# nixie-uhr.net
KiCad netlist of a schematic drawn in EAGLE
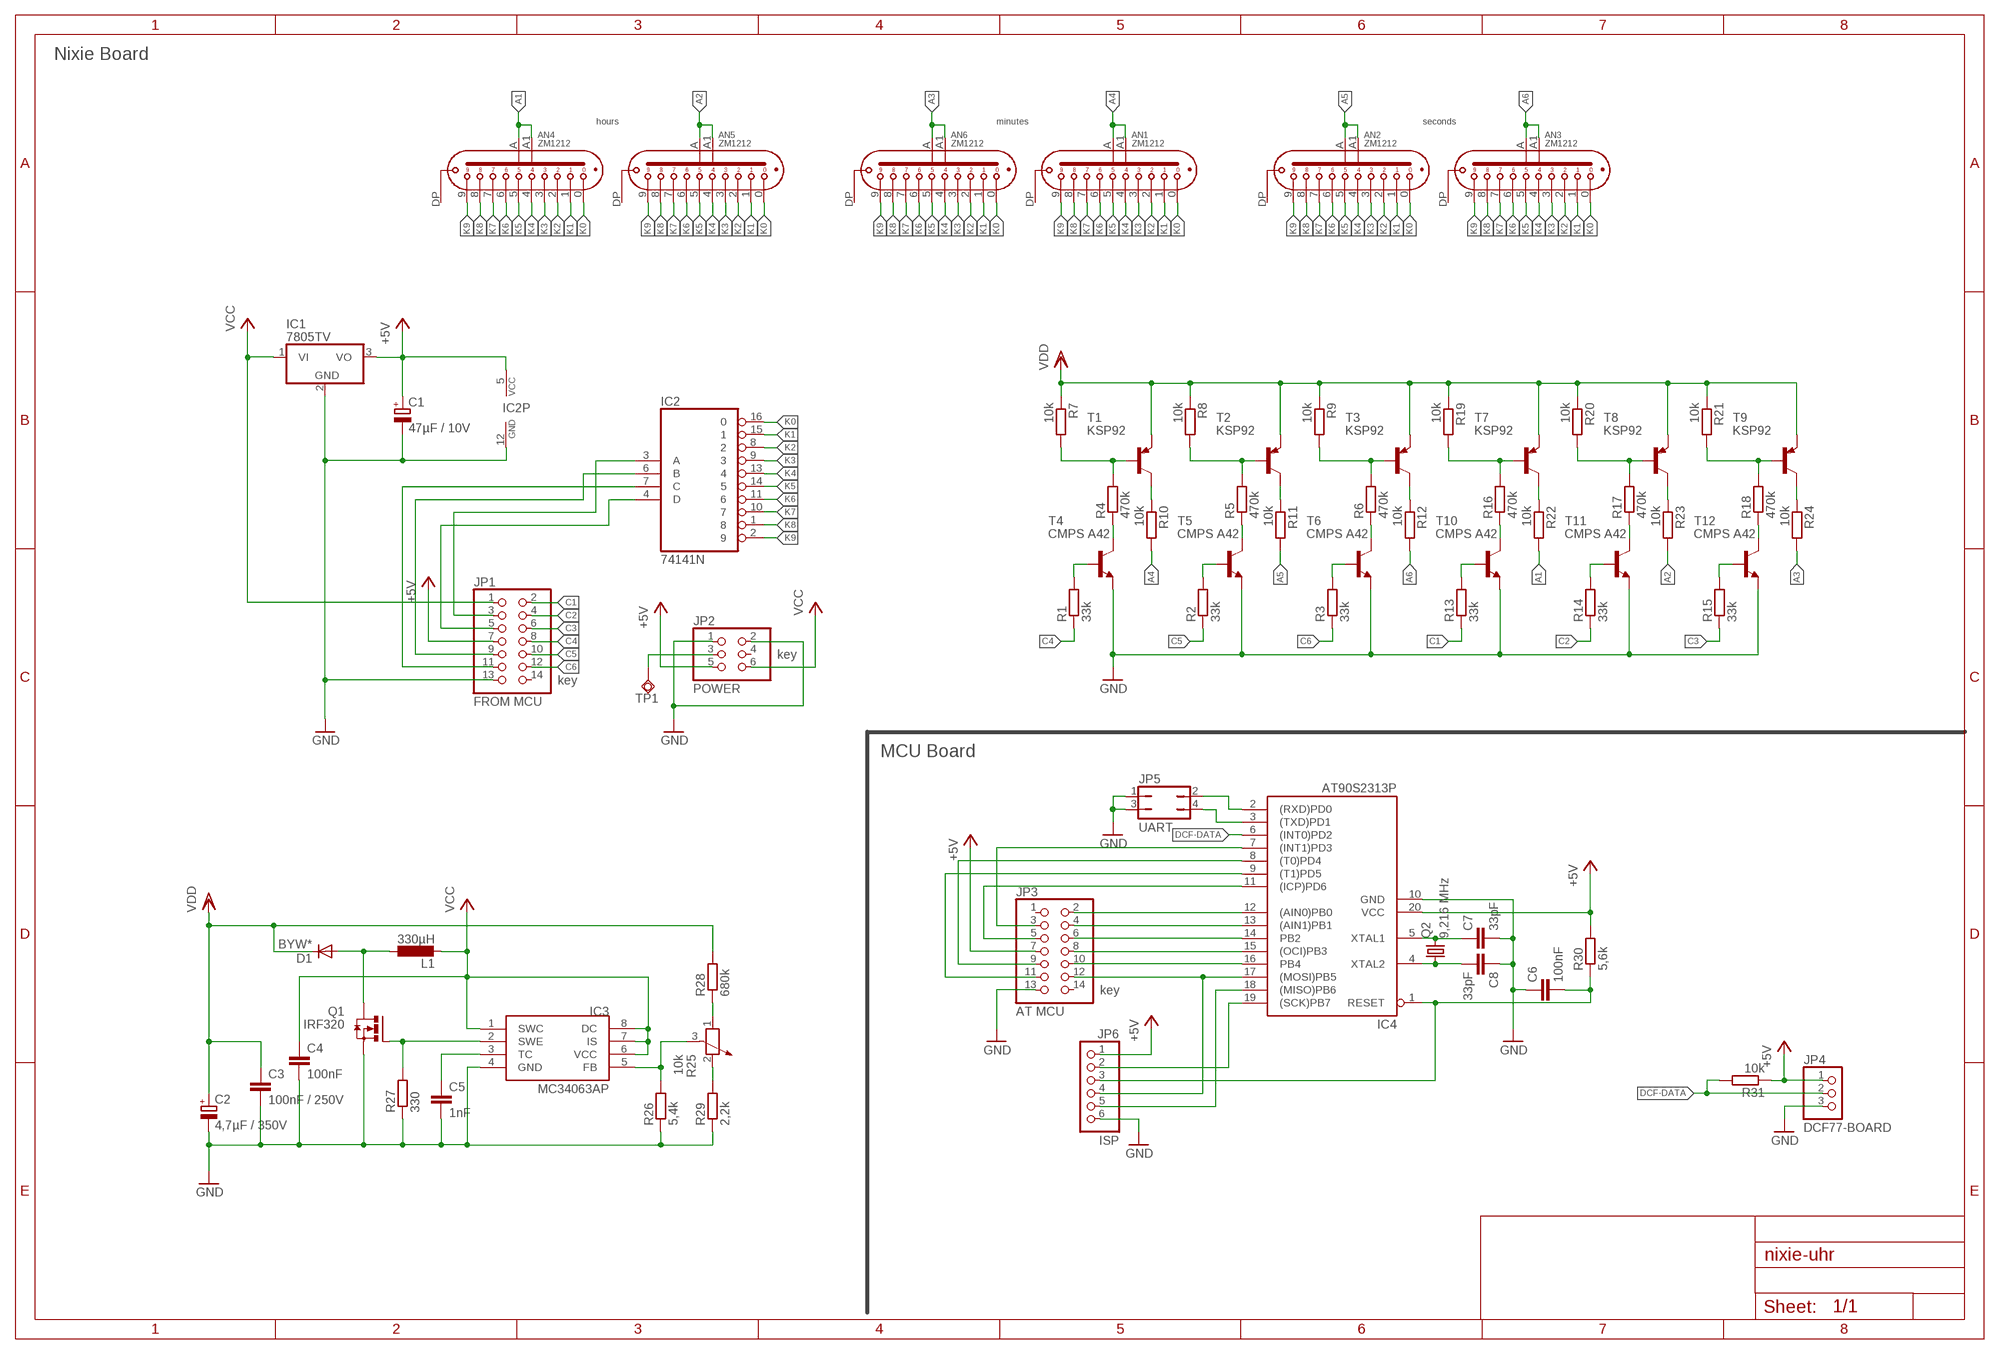
[diagram p0: schematic, sheet 1]

(export (version "E")
  (design (tool "Eeschema 10.0.6"))
  (components
    (comp (ref "AN1")
      (value "ZM1212")
      (footprint "eagle-import:ZM1000")
      (libsource (lib "eagle-import") (part "ZM1000"))
    )
    (comp (ref "AN2")
      (value "ZM1212")
      (footprint "eagle-import:ZM1000")
      (libsource (lib "eagle-import") (part "ZM1000"))
    )
    (comp (ref "AN3")
      (value "ZM1212")
      (footprint "eagle-import:ZM1000")
      (libsource (lib "eagle-import") (part "ZM1000"))
    )
    (comp (ref "AN4")
      (value "ZM1212")
      (footprint "eagle-import:ZM1000")
      (libsource (lib "eagle-import") (part "ZM1000"))
    )
    (comp (ref "AN5")
      (value "ZM1212")
      (footprint "eagle-import:ZM1000")
      (libsource (lib "eagle-import") (part "ZM1000"))
    )
    (comp (ref "AN6")
      (value "ZM1212")
      (footprint "eagle-import:ZM1000")
      (libsource (lib "eagle-import") (part "ZM1000"))
    )
    (comp (ref "C1")
      (value "47µF / 10V")
      (footprint "eagle-import:E2,5-5")
      (libsource (lib "eagle-import") (part "CPOL-EUE2.5-5"))
    )
    (comp (ref "C2")
      (value "4,7µF / 350V")
      (footprint "eagle-import:E30-10")
      (libsource (lib "eagle-import") (part "CPOL-EUE30-10AXIAL"))
    )
    (comp (ref "C3")
      (value "100nF / 250V")
      (footprint "eagle-import:C075-052X106")
      (libsource (lib "eagle-import") (part "C-EU075-052X106"))
    )
    (comp (ref "C4")
      (value "100nF")
      (footprint "eagle-import:C050-024X044")
      (libsource (lib "eagle-import") (part "C-EU050-024X044"))
    )
    (comp (ref "C5")
      (value "1nF")
      (footprint "eagle-import:C050-024X044")
      (libsource (lib "eagle-import") (part "C-EU050-024X044"))
    )
    (comp (ref "C6")
      (value "100nF")
      (footprint "eagle-import:C050-024X044")
      (libsource (lib "eagle-import") (part "C-EU050-024X044"))
    )
    (comp (ref "C7")
      (value "33pF")
      (footprint "eagle-import:C050-024X044")
      (libsource (lib "eagle-import") (part "C-EU050-024X044"))
    )
    (comp (ref "C8")
      (value "33pF")
      (footprint "eagle-import:C050-024X044")
      (libsource (lib "eagle-import") (part "C-EU050-024X044"))
    )
    (comp (ref "D1")
      (value "BYW*")
      (footprint "eagle-import:DO204-10")
      (libsource (lib "eagle-import") (part "BYW32"))
    )
    (comp (ref "IC1")
      (value "7805TV")
      (footprint "eagle-import:TO220V")
      (libsource (lib "eagle-import") (part "78TV05"))
    )
    (comp (ref "IC2")
      (value "74141N")
      (footprint "eagle-import:DIL16")
      (libsource (lib "eagle-import") (part "74141N"))
    )
    (comp (ref "IC3")
      (value "MC34063AP")
      (footprint "eagle-import:DIL08")
      (libsource (lib "eagle-import") (part "MC34063AP"))
    )
    (comp (ref "IC4")
      (value "AT90S2313P")
      (footprint "eagle-import:DIL20")
      (libsource (lib "eagle-import") (part "AT90S2313P"))
    )
    (comp (ref "JP1")
      (value "FROM MCU")
      (footprint "eagle-import:2X07")
      (libsource (lib "eagle-import") (part "PINHD-2X7"))
    )
    (comp (ref "JP2")
      (value "POWER")
      (footprint "eagle-import:2X03")
      (libsource (lib "eagle-import") (part "PINHD-2X3"))
    )
    (comp (ref "JP3")
      (value "AT MCU")
      (footprint "eagle-import:2X07")
      (libsource (lib "eagle-import") (part "PINHD-2X7"))
    )
    (comp (ref "JP4")
      (value "DCF77-BOARD")
      (footprint "eagle-import:1X03")
      (libsource (lib "eagle-import") (part "PINHD-1X3"))
    )
    (comp (ref "JP5")
      (value "UART")
      (footprint "eagle-import:JP2Q")
      (libsource (lib "eagle-import") (part "JP2Q"))
    )
    (comp (ref "JP6")
      (value "ISP")
      (footprint "eagle-import:1X06_90")
      (libsource (lib "eagle-import") (part "PINHD-1X6/90"))
    )
    (comp (ref "L1")
      (value "330µH")
      (footprint "eagle-import:0207_7")
      (libsource (lib "eagle-import") (part "L-EU0207/7"))
    )
    (comp (ref "Q1")
      (value "IRF320")
      (footprint "eagle-import:D2PACK")
      (libsource (lib "eagle-import") (part "IRF3704S"))
    )
    (comp (ref "Q2")
      (value "9,216 MHz")
      (footprint "eagle-import:HC49U-H")
      (libsource (lib "eagle-import") (part "CRYSTALHC49U-H"))
    )
    (comp (ref "R1")
      (value "33k")
      (footprint "eagle-import:0204_5")
      (libsource (lib "eagle-import") (part "R-EU_0204/5"))
    )
    (comp (ref "R2")
      (value "33k")
      (footprint "eagle-import:0204_5")
      (libsource (lib "eagle-import") (part "R-EU_0204/5"))
    )
    (comp (ref "R3")
      (value "33k")
      (footprint "eagle-import:0204_5")
      (libsource (lib "eagle-import") (part "R-EU_0204/5"))
    )
    (comp (ref "R4")
      (value "470k")
      (footprint "eagle-import:0204_5")
      (libsource (lib "eagle-import") (part "R-EU_0204/5"))
    )
    (comp (ref "R5")
      (value "470k")
      (footprint "eagle-import:0204_5")
      (libsource (lib "eagle-import") (part "R-EU_0204/5"))
    )
    (comp (ref "R6")
      (value "470k")
      (footprint "eagle-import:0204_5")
      (libsource (lib "eagle-import") (part "R-EU_0204/5"))
    )
    (comp (ref "R7")
      (value "10k")
      (footprint "eagle-import:0204_5")
      (libsource (lib "eagle-import") (part "R-EU_0204/5"))
    )
    (comp (ref "R8")
      (value "10k")
      (footprint "eagle-import:0204_5")
      (libsource (lib "eagle-import") (part "R-EU_0204/5"))
    )
    (comp (ref "R9")
      (value "10k")
      (footprint "eagle-import:0204_5")
      (libsource (lib "eagle-import") (part "R-EU_0204/5"))
    )
    (comp (ref "R10")
      (value "10k")
      (footprint "eagle-import:0204_5")
      (libsource (lib "eagle-import") (part "R-EU_0204/5"))
    )
    (comp (ref "R11")
      (value "10k")
      (footprint "eagle-import:0204_5")
      (libsource (lib "eagle-import") (part "R-EU_0204/5"))
    )
    (comp (ref "R12")
      (value "10k")
      (footprint "eagle-import:0204_5")
      (libsource (lib "eagle-import") (part "R-EU_0204/5"))
    )
    (comp (ref "R13")
      (value "33k")
      (footprint "eagle-import:0204_5")
      (libsource (lib "eagle-import") (part "R-EU_0204/5"))
    )
    (comp (ref "R14")
      (value "33k")
      (footprint "eagle-import:0204_5")
      (libsource (lib "eagle-import") (part "R-EU_0204/5"))
    )
    (comp (ref "R15")
      (value "33k")
      (footprint "eagle-import:0204_5")
      (libsource (lib "eagle-import") (part "R-EU_0204/5"))
    )
    (comp (ref "R16")
      (value "470k")
      (footprint "eagle-import:0204_5")
      (libsource (lib "eagle-import") (part "R-EU_0204/5"))
    )
    (comp (ref "R17")
      (value "470k")
      (footprint "eagle-import:0204_5")
      (libsource (lib "eagle-import") (part "R-EU_0204/5"))
    )
    (comp (ref "R18")
      (value "470k")
      (footprint "eagle-import:0204_5")
      (libsource (lib "eagle-import") (part "R-EU_0204/5"))
    )
    (comp (ref "R19")
      (value "10k")
      (footprint "eagle-import:0204_5")
      (libsource (lib "eagle-import") (part "R-EU_0204/5"))
    )
    (comp (ref "R20")
      (value "10k")
      (footprint "eagle-import:0204_5")
      (libsource (lib "eagle-import") (part "R-EU_0204/5"))
    )
    (comp (ref "R21")
      (value "10k")
      (footprint "eagle-import:0204_5")
      (libsource (lib "eagle-import") (part "R-EU_0204/5"))
    )
    (comp (ref "R22")
      (value "10k")
      (footprint "eagle-import:0204_5")
      (libsource (lib "eagle-import") (part "R-EU_0204/5"))
    )
    (comp (ref "R23")
      (value "10k")
      (footprint "eagle-import:0204_5")
      (libsource (lib "eagle-import") (part "R-EU_0204/5"))
    )
    (comp (ref "R24")
      (value "10k")
      (footprint "eagle-import:0204_5")
      (libsource (lib "eagle-import") (part "R-EU_0204/5"))
    )
    (comp (ref "R25")
      (value "10k")
      (footprint "eagle-import:PT-SPIN")
      (libsource (lib "eagle-import") (part "POTENTIOMETER_PT_SPIN"))
    )
    (comp (ref "R26")
      (value "5,4k")
      (footprint "eagle-import:0207_7")
      (libsource (lib "eagle-import") (part "R-EU_0207/7"))
    )
    (comp (ref "R27")
      (value "330")
      (footprint "eagle-import:0207_7")
      (libsource (lib "eagle-import") (part "R-EU_0207/7"))
    )
    (comp (ref "R28")
      (value "680k")
      (footprint "eagle-import:0309_12")
      (libsource (lib "eagle-import") (part "R-EU_0309/12"))
    )
    (comp (ref "R29")
      (value "2,2k")
      (footprint "eagle-import:0309_12")
      (libsource (lib "eagle-import") (part "R-EU_0309/12"))
    )
    (comp (ref "R30")
      (value "5,6k")
      (footprint "eagle-import:0204_5")
      (libsource (lib "eagle-import") (part "R-EU_0204/5"))
    )
    (comp (ref "R31")
      (value "10k")
      (footprint "eagle-import:0204_5")
      (libsource (lib "eagle-import") (part "R-EU_0204/5"))
    )
    (comp (ref "T1")
      (value "KSP92")
      (footprint "eagle-import:TO92")
      (libsource (lib "eagle-import") (part "-PNP-TO92"))
    )
    (comp (ref "T2")
      (value "KSP92")
      (footprint "eagle-import:TO92")
      (libsource (lib "eagle-import") (part "-PNP-TO92"))
    )
    (comp (ref "T3")
      (value "KSP92")
      (footprint "eagle-import:TO92")
      (libsource (lib "eagle-import") (part "-PNP-TO92"))
    )
    (comp (ref "T4")
      (value "CMPS A42")
      (footprint "eagle-import:TO92-CBE")
      (libsource (lib "eagle-import") (part "-NPN-TO92-CBEMPSA42"))
    )
    (comp (ref "T5")
      (value "CMPS A42")
      (footprint "eagle-import:TO92-CBE")
      (libsource (lib "eagle-import") (part "-NPN-TO92-CBEMPSA42"))
    )
    (comp (ref "T6")
      (value "CMPS A42")
      (footprint "eagle-import:TO92-CBE")
      (libsource (lib "eagle-import") (part "-NPN-TO92-CBEMPSA42"))
    )
    (comp (ref "T7")
      (value "KSP92")
      (footprint "eagle-import:TO92")
      (libsource (lib "eagle-import") (part "-PNP-TO92"))
    )
    (comp (ref "T8")
      (value "KSP92")
      (footprint "eagle-import:TO92")
      (libsource (lib "eagle-import") (part "-PNP-TO92"))
    )
    (comp (ref "T9")
      (value "KSP92")
      (footprint "eagle-import:TO92")
      (libsource (lib "eagle-import") (part "-PNP-TO92"))
    )
    (comp (ref "T10")
      (value "CMPS A42")
      (footprint "eagle-import:TO92-CBE")
      (libsource (lib "eagle-import") (part "-NPN-TO92-CBEMPSA42"))
    )
    (comp (ref "T11")
      (value "CMPS A42")
      (footprint "eagle-import:TO92-CBE")
      (libsource (lib "eagle-import") (part "-NPN-TO92-CBEMPSA42"))
    )
    (comp (ref "T12")
      (value "CMPS A42")
      (footprint "eagle-import:TO92-CBE")
      (libsource (lib "eagle-import") (part "-NPN-TO92-CBEMPSA42"))
    )
    (comp (ref "TP1")
      (value "TPSQPAD1-17")
      (footprint "eagle-import:P1-17")
      (libsource (lib "eagle-import") (part "TPSQPAD1-17"))
    )
  )
  (nets
    (net (code "1") (name "+5V") (class "Default")
      (node (ref "C1") (pin "+") (pinfunction "+_+") (pintype "passive"))
      (node (ref "IC1") (pin "3") (pinfunction "VO_3") (pintype "passive"))
      (node (ref "IC2") (pin "5") (pinfunction "VCC_5") (pintype "power_in"))
      (node (ref "IC4") (pin "20") (pinfunction "VCC_20") (pintype "power_in"))
      (node (ref "JP1") (pin "7") (pinfunction "7_7") (pintype "passive"))
      (node (ref "JP2") (pin "5") (pinfunction "5_5") (pintype "passive"))
      (node (ref "JP3") (pin "7") (pinfunction "7_7") (pintype "passive"))
      (node (ref "JP4") (pin "1") (pinfunction "1_1") (pintype "passive"))
      (node (ref "JP6") (pin "1") (pinfunction "1_1") (pintype "passive"))
      (node (ref "R30") (pin "2") (pinfunction "2_2") (pintype "passive"))
      (node (ref "R31") (pin "1") (pinfunction "1_1") (pintype "passive"))
    )
    (net (code "2") (name "A1") (class "Default")
      (node (ref "AN4") (pin "A") (pinfunction "A1_A") (pintype "passive"))
      (node (ref "AN4") (pin "A1") (pinfunction "A2_A1") (pintype "passive"))
      (node (ref "R22") (pin "2") (pinfunction "2_2") (pintype "passive"))
    )
    (net (code "3") (name "A2") (class "Default")
      (node (ref "AN5") (pin "A") (pinfunction "A1_A") (pintype "passive"))
      (node (ref "AN5") (pin "A1") (pinfunction "A2_A1") (pintype "passive"))
      (node (ref "R23") (pin "2") (pinfunction "2_2") (pintype "passive"))
    )
    (net (code "4") (name "A3") (class "Default")
      (node (ref "AN6") (pin "A") (pinfunction "A1_A") (pintype "passive"))
      (node (ref "AN6") (pin "A1") (pinfunction "A2_A1") (pintype "passive"))
      (node (ref "R24") (pin "2") (pinfunction "2_2") (pintype "passive"))
    )
    (net (code "5") (name "A4") (class "Default")
      (node (ref "AN1") (pin "A") (pinfunction "A1_A") (pintype "passive"))
      (node (ref "AN1") (pin "A1") (pinfunction "A2_A1") (pintype "passive"))
      (node (ref "R10") (pin "2") (pinfunction "2_2") (pintype "passive"))
    )
    (net (code "6") (name "A5") (class "Default")
      (node (ref "AN2") (pin "A") (pinfunction "A1_A") (pintype "passive"))
      (node (ref "AN2") (pin "A1") (pinfunction "A2_A1") (pintype "passive"))
      (node (ref "R11") (pin "2") (pinfunction "2_2") (pintype "passive"))
    )
    (net (code "7") (name "A6") (class "Default")
      (node (ref "AN3") (pin "A") (pinfunction "A1_A") (pintype "passive"))
      (node (ref "AN3") (pin "A1") (pinfunction "A2_A1") (pintype "passive"))
      (node (ref "R12") (pin "2") (pinfunction "2_2") (pintype "passive"))
    )
    (net (code "8") (name "C1") (class "Default")
      (node (ref "JP1") (pin "2") (pinfunction "2_2") (pintype "passive"))
      (node (ref "R13") (pin "1") (pinfunction "1_1") (pintype "passive"))
    )
    (net (code "9") (name "C2") (class "Default")
      (node (ref "JP1") (pin "4") (pinfunction "4_4") (pintype "passive"))
      (node (ref "R14") (pin "1") (pinfunction "1_1") (pintype "passive"))
    )
    (net (code "10") (name "C3") (class "Default")
      (node (ref "JP1") (pin "6") (pinfunction "6_6") (pintype "passive"))
      (node (ref "R15") (pin "1") (pinfunction "1_1") (pintype "passive"))
    )
    (net (code "11") (name "C4") (class "Default")
      (node (ref "JP1") (pin "8") (pinfunction "8_8") (pintype "passive"))
      (node (ref "R1") (pin "1") (pinfunction "1_1") (pintype "passive"))
    )
    (net (code "12") (name "C5") (class "Default")
      (node (ref "JP1") (pin "10") (pinfunction "10_10") (pintype "passive"))
      (node (ref "R2") (pin "1") (pinfunction "1_1") (pintype "passive"))
    )
    (net (code "13") (name "C6") (class "Default")
      (node (ref "JP1") (pin "12") (pinfunction "12_12") (pintype "passive"))
      (node (ref "R3") (pin "1") (pinfunction "1_1") (pintype "passive"))
    )
    (net (code "14") (name "DCF-DATA") (class "Default")
      (node (ref "IC4") (pin "6") (pinfunction "(INT0)PD2_6") (pintype "bidirectional"))
      (node (ref "JP4") (pin "2") (pinfunction "2_2") (pintype "passive"))
      (node (ref "R31") (pin "2") (pinfunction "2_2") (pintype "passive"))
    )
    (net (code "15") (name "GND") (class "Default")
      (node (ref "C1") (pin "-") (pinfunction "-_-") (pintype "passive"))
      (node (ref "C2") (pin "-") (pinfunction "-_-") (pintype "passive"))
      (node (ref "C3") (pin "2") (pinfunction "2_2") (pintype "passive"))
      (node (ref "C4") (pin "2") (pinfunction "2_2") (pintype "passive"))
      (node (ref "C5") (pin "2") (pinfunction "2_2") (pintype "passive"))
      (node (ref "C6") (pin "1") (pinfunction "1_1") (pintype "passive"))
      (node (ref "C7") (pin "2") (pinfunction "2_2") (pintype "passive"))
      (node (ref "C8") (pin "1") (pinfunction "1_1") (pintype "passive"))
      (node (ref "IC1") (pin "2") (pinfunction "GND_2") (pintype "passive"))
      (node (ref "IC2") (pin "12") (pinfunction "GND_12") (pintype "power_in"))
      (node (ref "IC3") (pin "4") (pinfunction "GND_4") (pintype "passive"))
      (node (ref "IC4") (pin "10") (pinfunction "GND_10") (pintype "power_in"))
      (node (ref "JP1") (pin "13") (pinfunction "13_13") (pintype "passive"))
      (node (ref "JP2") (pin "1") (pinfunction "1_1") (pintype "passive"))
      (node (ref "JP2") (pin "2") (pinfunction "2_2") (pintype "passive"))
      (node (ref "JP3") (pin "13") (pinfunction "13_13") (pintype "passive"))
      (node (ref "JP4") (pin "3") (pinfunction "3_3") (pintype "passive"))
      (node (ref "JP5") (pin "1") (pinfunction "1_1") (pintype "passive"))
      (node (ref "JP5") (pin "3") (pinfunction "3_3") (pintype "passive"))
      (node (ref "JP6") (pin "6") (pinfunction "6_6") (pintype "passive"))
      (node (ref "Q1") (pin "3") (pinfunction "S_3") (pintype "passive"))
      (node (ref "R26") (pin "1") (pinfunction "1_1") (pintype "passive"))
      (node (ref "R27") (pin "1") (pinfunction "1_1") (pintype "passive"))
      (node (ref "R29") (pin "1") (pinfunction "1_1") (pintype "passive"))
      (node (ref "T10") (pin "E") (pinfunction "E_E") (pintype "passive"))
      (node (ref "T11") (pin "E") (pinfunction "E_E") (pintype "passive"))
      (node (ref "T12") (pin "E") (pinfunction "E_E") (pintype "passive"))
      (node (ref "T4") (pin "E") (pinfunction "E_E") (pintype "passive"))
      (node (ref "T5") (pin "E") (pinfunction "E_E") (pintype "passive"))
      (node (ref "T6") (pin "E") (pinfunction "E_E") (pintype "passive"))
    )
    (net (code "16") (name "K0") (class "Default")
      (node (ref "AN1") (pin "0") (pinfunction "0_0") (pintype "passive"))
      (node (ref "AN2") (pin "0") (pinfunction "0_0") (pintype "passive"))
      (node (ref "AN3") (pin "0") (pinfunction "0_0") (pintype "passive"))
      (node (ref "AN4") (pin "0") (pinfunction "0_0") (pintype "passive"))
      (node (ref "AN5") (pin "0") (pinfunction "0_0") (pintype "passive"))
      (node (ref "AN6") (pin "0") (pinfunction "0_0") (pintype "passive"))
      (node (ref "IC2") (pin "16") (pinfunction "0_16") (pintype "open_collector"))
    )
    (net (code "17") (name "K1") (class "Default")
      (node (ref "AN1") (pin "1") (pinfunction "1_1") (pintype "passive"))
      (node (ref "AN2") (pin "1") (pinfunction "1_1") (pintype "passive"))
      (node (ref "AN3") (pin "1") (pinfunction "1_1") (pintype "passive"))
      (node (ref "AN4") (pin "1") (pinfunction "1_1") (pintype "passive"))
      (node (ref "AN5") (pin "1") (pinfunction "1_1") (pintype "passive"))
      (node (ref "AN6") (pin "1") (pinfunction "1_1") (pintype "passive"))
      (node (ref "IC2") (pin "15") (pinfunction "1_15") (pintype "open_collector"))
    )
    (net (code "18") (name "K2") (class "Default")
      (node (ref "AN1") (pin "2") (pinfunction "2_2") (pintype "passive"))
      (node (ref "AN2") (pin "2") (pinfunction "2_2") (pintype "passive"))
      (node (ref "AN3") (pin "2") (pinfunction "2_2") (pintype "passive"))
      (node (ref "AN4") (pin "2") (pinfunction "2_2") (pintype "passive"))
      (node (ref "AN5") (pin "2") (pinfunction "2_2") (pintype "passive"))
      (node (ref "AN6") (pin "2") (pinfunction "2_2") (pintype "passive"))
      (node (ref "IC2") (pin "8") (pinfunction "2_8") (pintype "open_collector"))
    )
    (net (code "19") (name "K3") (class "Default")
      (node (ref "AN1") (pin "3") (pinfunction "3_3") (pintype "passive"))
      (node (ref "AN2") (pin "3") (pinfunction "3_3") (pintype "passive"))
      (node (ref "AN3") (pin "3") (pinfunction "3_3") (pintype "passive"))
      (node (ref "AN4") (pin "3") (pinfunction "3_3") (pintype "passive"))
      (node (ref "AN5") (pin "3") (pinfunction "3_3") (pintype "passive"))
      (node (ref "AN6") (pin "3") (pinfunction "3_3") (pintype "passive"))
      (node (ref "IC2") (pin "9") (pinfunction "3_9") (pintype "open_collector"))
    )
    (net (code "20") (name "K4") (class "Default")
      (node (ref "AN1") (pin "4") (pinfunction "4_4") (pintype "passive"))
      (node (ref "AN2") (pin "4") (pinfunction "4_4") (pintype "passive"))
      (node (ref "AN3") (pin "4") (pinfunction "4_4") (pintype "passive"))
      (node (ref "AN4") (pin "4") (pinfunction "4_4") (pintype "passive"))
      (node (ref "AN5") (pin "4") (pinfunction "4_4") (pintype "passive"))
      (node (ref "AN6") (pin "4") (pinfunction "4_4") (pintype "passive"))
      (node (ref "IC2") (pin "13") (pinfunction "4_13") (pintype "open_collector"))
    )
    (net (code "21") (name "K5") (class "Default")
      (node (ref "AN1") (pin "5") (pinfunction "5_5") (pintype "passive"))
      (node (ref "AN2") (pin "5") (pinfunction "5_5") (pintype "passive"))
      (node (ref "AN3") (pin "5") (pinfunction "5_5") (pintype "passive"))
      (node (ref "AN4") (pin "5") (pinfunction "5_5") (pintype "passive"))
      (node (ref "AN5") (pin "5") (pinfunction "5_5") (pintype "passive"))
      (node (ref "AN6") (pin "5") (pinfunction "5_5") (pintype "passive"))
      (node (ref "IC2") (pin "14") (pinfunction "5_14") (pintype "open_collector"))
    )
    (net (code "22") (name "K6") (class "Default")
      (node (ref "AN1") (pin "6") (pinfunction "6_6") (pintype "passive"))
      (node (ref "AN2") (pin "6") (pinfunction "6_6") (pintype "passive"))
      (node (ref "AN3") (pin "6") (pinfunction "6_6") (pintype "passive"))
      (node (ref "AN4") (pin "6") (pinfunction "6_6") (pintype "passive"))
      (node (ref "AN5") (pin "6") (pinfunction "6_6") (pintype "passive"))
      (node (ref "AN6") (pin "6") (pinfunction "6_6") (pintype "passive"))
      (node (ref "IC2") (pin "11") (pinfunction "6_11") (pintype "open_collector"))
    )
    (net (code "23") (name "K7") (class "Default")
      (node (ref "AN1") (pin "7") (pinfunction "7_7") (pintype "passive"))
      (node (ref "AN2") (pin "7") (pinfunction "7_7") (pintype "passive"))
      (node (ref "AN3") (pin "7") (pinfunction "7_7") (pintype "passive"))
      (node (ref "AN4") (pin "7") (pinfunction "7_7") (pintype "passive"))
      (node (ref "AN5") (pin "7") (pinfunction "7_7") (pintype "passive"))
      (node (ref "AN6") (pin "7") (pinfunction "7_7") (pintype "passive"))
      (node (ref "IC2") (pin "10") (pinfunction "7_10") (pintype "open_collector"))
    )
    (net (code "24") (name "K8") (class "Default")
      (node (ref "AN1") (pin "8") (pinfunction "8_8") (pintype "passive"))
      (node (ref "AN2") (pin "8") (pinfunction "8_8") (pintype "passive"))
      (node (ref "AN3") (pin "8") (pinfunction "8_8") (pintype "passive"))
      (node (ref "AN4") (pin "8") (pinfunction "8_8") (pintype "passive"))
      (node (ref "AN5") (pin "8") (pinfunction "8_8") (pintype "passive"))
      (node (ref "AN6") (pin "8") (pinfunction "8_8") (pintype "passive"))
      (node (ref "IC2") (pin "1") (pinfunction "8_1") (pintype "open_collector"))
    )
    (net (code "25") (name "K9") (class "Default")
      (node (ref "AN1") (pin "9") (pinfunction "9_9") (pintype "passive"))
      (node (ref "AN2") (pin "9") (pinfunction "9_9") (pintype "passive"))
      (node (ref "AN3") (pin "9") (pinfunction "9_9") (pintype "passive"))
      (node (ref "AN4") (pin "9") (pinfunction "9_9") (pintype "passive"))
      (node (ref "AN5") (pin "9") (pinfunction "9_9") (pintype "passive"))
      (node (ref "AN6") (pin "9") (pinfunction "9_9") (pintype "passive"))
      (node (ref "IC2") (pin "2") (pinfunction "9_2") (pintype "open_collector"))
    )
    (net (code "26") (name "Net-(IC2A-A)") (class "Default")
      (node (ref "IC2") (pin "3") (pinfunction "A_3") (pintype "input"))
      (node (ref "JP1") (pin "3") (pinfunction "3_3") (pintype "passive"))
    )
    (net (code "27") (name "Net-(IC2A-B)") (class "Default")
      (node (ref "IC2") (pin "6") (pinfunction "B_6") (pintype "input"))
      (node (ref "JP1") (pin "9") (pinfunction "9_9") (pintype "passive"))
    )
    (net (code "28") (name "Net-(IC2A-C)") (class "Default")
      (node (ref "IC2") (pin "7") (pinfunction "C_7") (pintype "input"))
      (node (ref "JP1") (pin "11") (pinfunction "11_11") (pintype "passive"))
    )
    (net (code "29") (name "Net-(IC2A-D)") (class "Default")
      (node (ref "IC2") (pin "4") (pinfunction "D_4") (pintype "input"))
      (node (ref "JP1") (pin "5") (pinfunction "5_5") (pintype "passive"))
    )
    (net (code "30") (name "Net-(IC3-FB)") (class "Default")
      (node (ref "IC3") (pin "5") (pinfunction "FB_5") (pintype "passive"))
      (node (ref "R25") (pin "3") (pinfunction "3_3") (pintype "passive"))
      (node (ref "R26") (pin "2") (pinfunction "2_2") (pintype "passive"))
    )
    (net (code "31") (name "Net-(IC3-SWE)") (class "Default")
      (node (ref "IC3") (pin "2") (pinfunction "SWE_2") (pintype "passive"))
      (node (ref "Q1") (pin "1") (pinfunction "G_1") (pintype "passive"))
      (node (ref "R27") (pin "2") (pinfunction "2_2") (pintype "passive"))
    )
    (net (code "32") (name "Net-(IC3-TC)") (class "Default")
      (node (ref "C5") (pin "1") (pinfunction "1_1") (pintype "passive"))
      (node (ref "IC3") (pin "3") (pinfunction "TC_3") (pintype "passive"))
    )
    (net (code "33") (name "Net-(IC4-(AIN0)PB0)") (class "Default")
      (node (ref "IC4") (pin "12") (pinfunction "(AIN0)PB0_12") (pintype "bidirectional"))
      (node (ref "JP3") (pin "2") (pinfunction "2_2") (pintype "passive"))
    )
    (net (code "34") (name "Net-(IC4-(AIN1)PB1)") (class "Default")
      (node (ref "IC4") (pin "13") (pinfunction "(AIN1)PB1_13") (pintype "bidirectional"))
      (node (ref "JP3") (pin "4") (pinfunction "4_4") (pintype "passive"))
    )
    (net (code "35") (name "Net-(IC4-(ICP)PD6)") (class "Default")
      (node (ref "IC4") (pin "11") (pinfunction "(ICP)PD6_11") (pintype "bidirectional"))
      (node (ref "JP3") (pin "5") (pinfunction "5_5") (pintype "passive"))
    )
    (net (code "36") (name "Net-(IC4-(INT1)PD3)") (class "Default")
      (node (ref "IC4") (pin "7") (pinfunction "(INT1)PD3_7") (pintype "bidirectional"))
      (node (ref "JP3") (pin "3") (pinfunction "3_3") (pintype "passive"))
    )
    (net (code "37") (name "Net-(IC4-(MISO)PB6)") (class "Default")
      (node (ref "IC4") (pin "18") (pinfunction "(MISO)PB6_18") (pintype "bidirectional"))
      (node (ref "JP6") (pin "5") (pinfunction "5_5") (pintype "passive"))
    )
    (net (code "38") (name "Net-(IC4-(MOSI)PB5)") (class "Default")
      (node (ref "IC4") (pin "17") (pinfunction "(MOSI)PB5_17") (pintype "bidirectional"))
      (node (ref "JP3") (pin "12") (pinfunction "12_12") (pintype "passive"))
      (node (ref "JP6") (pin "4") (pinfunction "4_4") (pintype "passive"))
    )
    (net (code "39") (name "Net-(IC4-(OCI)PB3)") (class "Default")
      (node (ref "IC4") (pin "15") (pinfunction "(OCI)PB3_15") (pintype "bidirectional"))
      (node (ref "JP3") (pin "8") (pinfunction "8_8") (pintype "passive"))
    )
    (net (code "40") (name "Net-(IC4-(RXD)PD0)") (class "Default")
      (node (ref "IC4") (pin "2") (pinfunction "(RXD)PD0_2") (pintype "bidirectional"))
      (node (ref "JP5") (pin "2") (pinfunction "2_2") (pintype "passive"))
    )
    (net (code "41") (name "Net-(IC4-(SCK)PB7)") (class "Default")
      (node (ref "IC4") (pin "19") (pinfunction "(SCK)PB7_19") (pintype "bidirectional"))
      (node (ref "JP6") (pin "2") (pinfunction "2_2") (pintype "passive"))
    )
    (net (code "42") (name "Net-(IC4-(T0)PD4)") (class "Default")
      (node (ref "IC4") (pin "8") (pinfunction "(T0)PD4_8") (pintype "bidirectional"))
      (node (ref "JP3") (pin "9") (pinfunction "9_9") (pintype "passive"))
    )
    (net (code "43") (name "Net-(IC4-(T1)PD5)") (class "Default")
      (node (ref "IC4") (pin "9") (pinfunction "(T1)PD5_9") (pintype "bidirectional"))
      (node (ref "JP3") (pin "11") (pinfunction "11_11") (pintype "passive"))
    )
    (net (code "44") (name "Net-(IC4-(TXD)PD1)") (class "Default")
      (node (ref "IC4") (pin "3") (pinfunction "(TXD)PD1_3") (pintype "bidirectional"))
      (node (ref "JP5") (pin "4") (pinfunction "4_4") (pintype "passive"))
    )
    (net (code "45") (name "Net-(IC4-PB2)") (class "Default")
      (node (ref "IC4") (pin "14") (pinfunction "PB2_14") (pintype "bidirectional"))
      (node (ref "JP3") (pin "6") (pinfunction "6_6") (pintype "passive"))
    )
    (net (code "46") (name "Net-(IC4-PB4)") (class "Default")
      (node (ref "IC4") (pin "16") (pinfunction "PB4_16") (pintype "bidirectional"))
      (node (ref "JP3") (pin "10") (pinfunction "10_10") (pintype "passive"))
    )
    (net (code "47") (name "Net-(IC4-RESET)") (class "Default")
      (node (ref "C6") (pin "2") (pinfunction "2_2") (pintype "passive"))
      (node (ref "IC4") (pin "1") (pinfunction "RESET_1") (pintype "bidirectional"))
      (node (ref "JP6") (pin "3") (pinfunction "3_3") (pintype "passive"))
      (node (ref "R30") (pin "1") (pinfunction "1_1") (pintype "passive"))
    )
    (net (code "48") (name "Net-(IC4-XTAL1)") (class "Default")
      (node (ref "C7") (pin "1") (pinfunction "1_1") (pintype "passive"))
      (node (ref "IC4") (pin "5") (pinfunction "XTAL1_5") (pintype "bidirectional"))
      (node (ref "Q2") (pin "2") (pinfunction "2_2") (pintype "passive"))
    )
    (net (code "49") (name "Net-(IC4-XTAL2)") (class "Default")
      (node (ref "C8") (pin "2") (pinfunction "2_2") (pintype "passive"))
      (node (ref "IC4") (pin "4") (pinfunction "XTAL2_4") (pintype "bidirectional"))
      (node (ref "Q2") (pin "1") (pinfunction "1_1") (pintype "passive"))
    )
    (net (code "50") (name "Net-(JP2-Pad3)") (class "Default")
      (node (ref "JP2") (pin "3") (pinfunction "3_3") (pintype "passive"))
      (node (ref "TP1") (pin "TP") (pinfunction "TP_TP") (pintype "input"))
    )
    (net (code "51") (name "Net-(Q1-D)") (class "Default")
      (node (ref "D1") (pin "A") (pinfunction "A_A") (pintype "passive"))
      (node (ref "L1") (pin "1") (pinfunction "1_1") (pintype "passive"))
      (node (ref "Q1") (pin "2") (pinfunction "D_2") (pintype "passive"))
    )
    (net (code "52") (name "Net-(R1-Pad2)") (class "Default")
      (node (ref "R1") (pin "2") (pinfunction "2_2") (pintype "passive"))
      (node (ref "T4") (pin "B") (pinfunction "B_B") (pintype "passive"))
    )
    (net (code "53") (name "Net-(R2-Pad2)") (class "Default")
      (node (ref "R2") (pin "2") (pinfunction "2_2") (pintype "passive"))
      (node (ref "T5") (pin "B") (pinfunction "B_B") (pintype "passive"))
    )
    (net (code "54") (name "Net-(R3-Pad2)") (class "Default")
      (node (ref "R3") (pin "2") (pinfunction "2_2") (pintype "passive"))
      (node (ref "T6") (pin "B") (pinfunction "B_B") (pintype "passive"))
    )
    (net (code "55") (name "Net-(R4-Pad1)") (class "Default")
      (node (ref "R4") (pin "1") (pinfunction "1_1") (pintype "passive"))
      (node (ref "T4") (pin "C") (pinfunction "C_C") (pintype "passive"))
    )
    (net (code "56") (name "Net-(R5-Pad1)") (class "Default")
      (node (ref "R5") (pin "1") (pinfunction "1_1") (pintype "passive"))
      (node (ref "T5") (pin "C") (pinfunction "C_C") (pintype "passive"))
    )
    (net (code "57") (name "Net-(R6-Pad1)") (class "Default")
      (node (ref "R6") (pin "1") (pinfunction "1_1") (pintype "passive"))
      (node (ref "T6") (pin "C") (pinfunction "C_C") (pintype "passive"))
    )
    (net (code "58") (name "Net-(R13-Pad2)") (class "Default")
      (node (ref "R13") (pin "2") (pinfunction "2_2") (pintype "passive"))
      (node (ref "T10") (pin "B") (pinfunction "B_B") (pintype "passive"))
    )
    (net (code "59") (name "Net-(R14-Pad2)") (class "Default")
      (node (ref "R14") (pin "2") (pinfunction "2_2") (pintype "passive"))
      (node (ref "T11") (pin "B") (pinfunction "B_B") (pintype "passive"))
    )
    (net (code "60") (name "Net-(R15-Pad2)") (class "Default")
      (node (ref "R15") (pin "2") (pinfunction "2_2") (pintype "passive"))
      (node (ref "T12") (pin "B") (pinfunction "B_B") (pintype "passive"))
    )
    (net (code "61") (name "Net-(R16-Pad1)") (class "Default")
      (node (ref "R16") (pin "1") (pinfunction "1_1") (pintype "passive"))
      (node (ref "T10") (pin "C") (pinfunction "C_C") (pintype "passive"))
    )
    (net (code "62") (name "Net-(R17-Pad1)") (class "Default")
      (node (ref "R17") (pin "1") (pinfunction "1_1") (pintype "passive"))
      (node (ref "T11") (pin "C") (pinfunction "C_C") (pintype "passive"))
    )
    (net (code "63") (name "Net-(R18-Pad1)") (class "Default")
      (node (ref "R18") (pin "1") (pinfunction "1_1") (pintype "passive"))
      (node (ref "T12") (pin "C") (pinfunction "C_C") (pintype "passive"))
    )
    (net (code "64") (name "Net-(R25-Pad1)") (class "Default")
      (node (ref "R25") (pin "1") (pinfunction "1_1") (pintype "passive"))
      (node (ref "R28") (pin "1") (pinfunction "1_1") (pintype "passive"))
    )
    (net (code "65") (name "Net-(R25-Pad2)") (class "Default")
      (node (ref "R25") (pin "2") (pinfunction "2_2") (pintype "passive"))
      (node (ref "R29") (pin "2") (pinfunction "2_2") (pintype "passive"))
    )
    (net (code "66") (name "Net-(T1-B)") (class "Default")
      (node (ref "R4") (pin "2") (pinfunction "2_2") (pintype "passive"))
      (node (ref "R7") (pin "2") (pinfunction "2_2") (pintype "passive"))
      (node (ref "T1") (pin "2") (pinfunction "B_2") (pintype "passive"))
    )
    (net (code "67") (name "Net-(T1-C)") (class "Default")
      (node (ref "R10") (pin "1") (pinfunction "1_1") (pintype "passive"))
      (node (ref "T1") (pin "3") (pinfunction "C_3") (pintype "passive"))
    )
    (net (code "68") (name "Net-(T2-B)") (class "Default")
      (node (ref "R5") (pin "2") (pinfunction "2_2") (pintype "passive"))
      (node (ref "R8") (pin "2") (pinfunction "2_2") (pintype "passive"))
      (node (ref "T2") (pin "2") (pinfunction "B_2") (pintype "passive"))
    )
    (net (code "69") (name "Net-(T2-C)") (class "Default")
      (node (ref "R11") (pin "1") (pinfunction "1_1") (pintype "passive"))
      (node (ref "T2") (pin "3") (pinfunction "C_3") (pintype "passive"))
    )
    (net (code "70") (name "Net-(T3-B)") (class "Default")
      (node (ref "R6") (pin "2") (pinfunction "2_2") (pintype "passive"))
      (node (ref "R9") (pin "2") (pinfunction "2_2") (pintype "passive"))
      (node (ref "T3") (pin "2") (pinfunction "B_2") (pintype "passive"))
    )
    (net (code "71") (name "Net-(T3-C)") (class "Default")
      (node (ref "R12") (pin "1") (pinfunction "1_1") (pintype "passive"))
      (node (ref "T3") (pin "3") (pinfunction "C_3") (pintype "passive"))
    )
    (net (code "72") (name "Net-(T7-B)") (class "Default")
      (node (ref "R16") (pin "2") (pinfunction "2_2") (pintype "passive"))
      (node (ref "R19") (pin "2") (pinfunction "2_2") (pintype "passive"))
      (node (ref "T7") (pin "2") (pinfunction "B_2") (pintype "passive"))
    )
    (net (code "73") (name "Net-(T7-C)") (class "Default")
      (node (ref "R22") (pin "1") (pinfunction "1_1") (pintype "passive"))
      (node (ref "T7") (pin "3") (pinfunction "C_3") (pintype "passive"))
    )
    (net (code "74") (name "Net-(T8-B)") (class "Default")
      (node (ref "R17") (pin "2") (pinfunction "2_2") (pintype "passive"))
      (node (ref "R20") (pin "2") (pinfunction "2_2") (pintype "passive"))
      (node (ref "T8") (pin "2") (pinfunction "B_2") (pintype "passive"))
    )
    (net (code "75") (name "Net-(T8-C)") (class "Default")
      (node (ref "R23") (pin "1") (pinfunction "1_1") (pintype "passive"))
      (node (ref "T8") (pin "3") (pinfunction "C_3") (pintype "passive"))
    )
    (net (code "76") (name "Net-(T9-B)") (class "Default")
      (node (ref "R18") (pin "2") (pinfunction "2_2") (pintype "passive"))
      (node (ref "R21") (pin "2") (pinfunction "2_2") (pintype "passive"))
      (node (ref "T9") (pin "2") (pinfunction "B_2") (pintype "passive"))
    )
    (net (code "77") (name "Net-(T9-C)") (class "Default")
      (node (ref "R24") (pin "1") (pinfunction "1_1") (pintype "passive"))
      (node (ref "T9") (pin "3") (pinfunction "C_3") (pintype "passive"))
    )
    (net (code "78") (name "VCC") (class "Default")
      (node (ref "C4") (pin "1") (pinfunction "1_1") (pintype "passive"))
      (node (ref "IC1") (pin "1") (pinfunction "VI_1") (pintype "input"))
      (node (ref "IC3") (pin "1") (pinfunction "SWC_1") (pintype "passive"))
      (node (ref "IC3") (pin "6") (pinfunction "VCC_6") (pintype "passive"))
      (node (ref "IC3") (pin "7") (pinfunction "IS_7") (pintype "passive"))
      (node (ref "IC3") (pin "8") (pinfunction "DC_8") (pintype "passive"))
      (node (ref "JP1") (pin "1") (pinfunction "1_1") (pintype "passive"))
      (node (ref "JP2") (pin "6") (pinfunction "6_6") (pintype "passive"))
      (node (ref "L1") (pin "2") (pinfunction "2_2") (pintype "passive"))
    )
    (net (code "79") (name "VDD") (class "Default")
      (node (ref "C2") (pin "+") (pinfunction "+_+") (pintype "passive"))
      (node (ref "C3") (pin "1") (pinfunction "1_1") (pintype "passive"))
      (node (ref "D1") (pin "C") (pinfunction "C_C") (pintype "passive"))
      (node (ref "R19") (pin "1") (pinfunction "1_1") (pintype "passive"))
      (node (ref "R20") (pin "1") (pinfunction "1_1") (pintype "passive"))
      (node (ref "R21") (pin "1") (pinfunction "1_1") (pintype "passive"))
      (node (ref "R28") (pin "2") (pinfunction "2_2") (pintype "passive"))
      (node (ref "R7") (pin "1") (pinfunction "1_1") (pintype "passive"))
      (node (ref "R8") (pin "1") (pinfunction "1_1") (pintype "passive"))
      (node (ref "R9") (pin "1") (pinfunction "1_1") (pintype "passive"))
      (node (ref "T1") (pin "1") (pinfunction "E_1") (pintype "passive"))
      (node (ref "T2") (pin "1") (pinfunction "E_1") (pintype "passive"))
      (node (ref "T3") (pin "1") (pinfunction "E_1") (pintype "passive"))
      (node (ref "T7") (pin "1") (pinfunction "E_1") (pintype "passive"))
      (node (ref "T8") (pin "1") (pinfunction "E_1") (pintype "passive"))
      (node (ref "T9") (pin "1") (pinfunction "E_1") (pintype "passive"))
    )
    (net (code "80") (name "unconnected-(AN1-DPL-PadDP)") (class "Default")
      (node (ref "AN1") (pin "DP") (pinfunction "DPL_DP") (pintype "passive"))
    )
    (net (code "81") (name "unconnected-(AN2-DPL-PadDP)") (class "Default")
      (node (ref "AN2") (pin "DP") (pinfunction "DPL_DP") (pintype "passive"))
    )
    (net (code "82") (name "unconnected-(AN3-DPL-PadDP)") (class "Default")
      (node (ref "AN3") (pin "DP") (pinfunction "DPL_DP") (pintype "passive"))
    )
    (net (code "83") (name "unconnected-(AN4-DPL-PadDP)") (class "Default")
      (node (ref "AN4") (pin "DP") (pinfunction "DPL_DP") (pintype "passive"))
    )
    (net (code "84") (name "unconnected-(AN5-DPL-PadDP)") (class "Default")
      (node (ref "AN5") (pin "DP") (pinfunction "DPL_DP") (pintype "passive"))
    )
    (net (code "85") (name "unconnected-(AN6-DPL-PadDP)") (class "Default")
      (node (ref "AN6") (pin "DP") (pinfunction "DPL_DP") (pintype "passive"))
    )
    (net (code "86") (name "unconnected-(JP1-Pad14)") (class "Default")
      (node (ref "JP1") (pin "14") (pinfunction "14_14") (pintype "passive"))
    )
    (net (code "87") (name "unconnected-(JP2-Pad4)") (class "Default")
      (node (ref "JP2") (pin "4") (pinfunction "4_4") (pintype "passive"))
    )
    (net (code "88") (name "unconnected-(JP3-Pad1)") (class "Default")
      (node (ref "JP3") (pin "1") (pinfunction "1_1") (pintype "passive"))
    )
    (net (code "89") (name "unconnected-(JP3-Pad14)") (class "Default")
      (node (ref "JP3") (pin "14") (pinfunction "14_14") (pintype "passive"))
    )
  )
)
